# SD_Card_Interface.net
KiCad netlist of a schematic drawn in Altium Designer
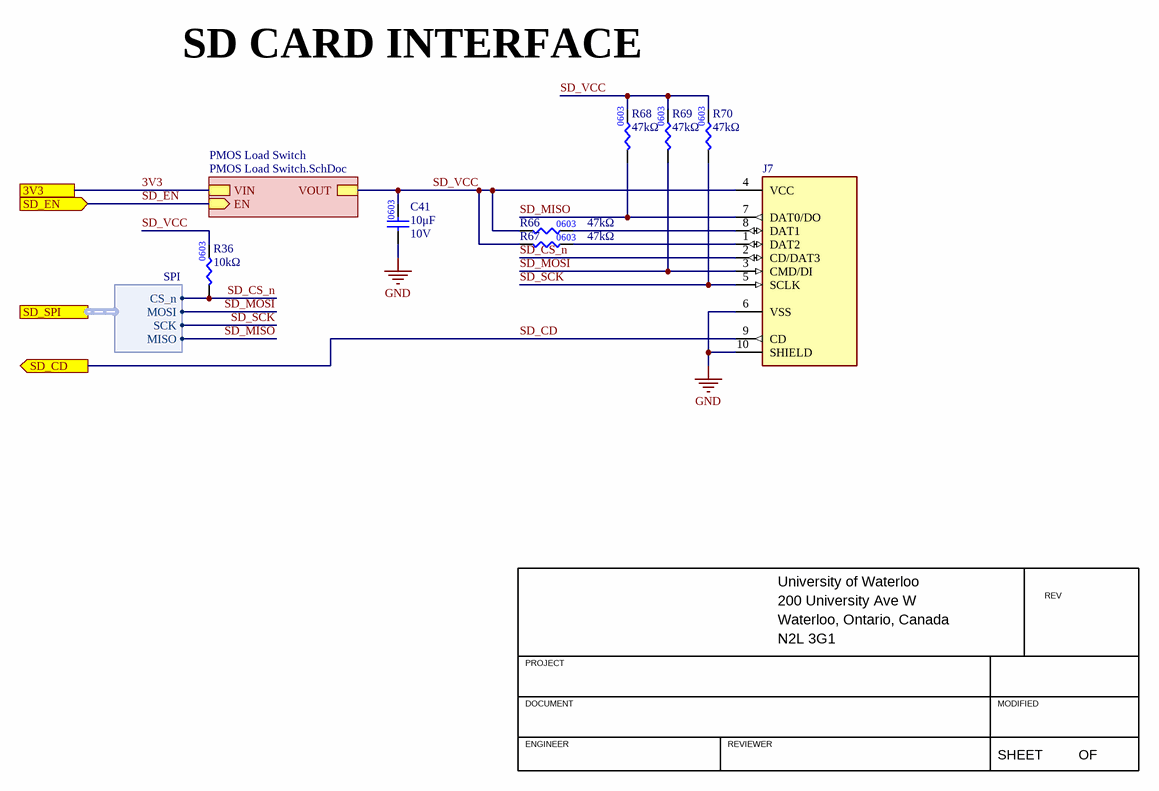
[diagram p0: SD Card Interface.SchDoc]

(export (version "E")
  (design (tool "Eeschema 10.0.6"))
  (components
    (comp (ref "C41")
      (value "10μF")
      (footprint "CAP0603")
      (description "CAP CER 10UF 10V X5R 0603")
      (fields (field (name "VOLTAGE RATING") "10V") (field (name "Comment") "CAP_10uF_10V_0603"))
      (libsource (lib "Personal_Schematic_Library_2022") (part "CAP_10uF_10V_0603"))
    )
    (comp (ref "J7")
      (value "CON_MICROSD_MOLEX")
      (footprint "MOLEX-5033981892")
      (description "CONN MICRO SD CARD R/A SMD")
      (libsource (lib "Personal_Schematic_Library_2022") (part "CON_MICROSD_MOLEX"))
    )
    (comp (ref "R36")
      (value "10kΩ")
      (footprint "RES0603")
      (description "RES 10K OHM 1% 1/8W 0603")
      (fields (field (name "Comment") "RES_10kΩ_0603_1%"))
      (libsource (lib "Personal_Schematic_Library_2022") (part "RES_10kΩ_0603_1%"))
    )
    (comp (ref "R66")
      (value "47kΩ")
      (footprint "RES0603")
      (description "RES 47K OHM 1% 1/10W 0603")
      (fields (field (name "Comment") "RES_47kΩ_0603_1%"))
      (libsource (lib "Personal_Schematic_Library_2022") (part "RES_47kΩ_0603_1%"))
    )
    (comp (ref "R67")
      (value "47kΩ")
      (footprint "RES0603")
      (description "RES 47K OHM 1% 1/10W 0603")
      (fields (field (name "Comment") "RES_47kΩ_0603_1%"))
      (libsource (lib "Personal_Schematic_Library_2022") (part "RES_47kΩ_0603_1%"))
    )
    (comp (ref "R68")
      (value "47kΩ")
      (footprint "RES0603")
      (description "RES 47K OHM 1% 1/10W 0603")
      (fields (field (name "Comment") "RES_47kΩ_0603_1%"))
      (libsource (lib "Personal_Schematic_Library_2022") (part "RES_47kΩ_0603_1%"))
    )
    (comp (ref "R69")
      (value "47kΩ")
      (footprint "RES0603")
      (description "RES 47K OHM 1% 1/10W 0603")
      (fields (field (name "Comment") "RES_47kΩ_0603_1%"))
      (libsource (lib "Personal_Schematic_Library_2022") (part "RES_47kΩ_0603_1%"))
    )
    (comp (ref "R70")
      (value "47kΩ")
      (footprint "RES0603")
      (description "RES 47K OHM 1% 1/10W 0603")
      (fields (field (name "Comment") "RES_47kΩ_0603_1%"))
      (libsource (lib "Personal_Schematic_Library_2022") (part "RES_47kΩ_0603_1%"))
    )
  )
  (nets
    (net (code "3") (name "/SD_CD") (class "Default")
      (node (ref "J7") (pin "9") (pinfunction "CD_9") (pintype "output"))
    )
    (net (code "4") (name "/SD_CS_n") (class "Default")
      (node (ref "J7") (pin "2") (pinfunction "CD/DAT3_2") (pintype "bidirectional"))
      (node (ref "R36") (pin "1") (pinfunction "1_1") (pintype "passive"))
    )
    (net (code "6") (name "/SD_MISO") (class "Default")
      (node (ref "J7") (pin "7") (pinfunction "DAT0/DO_7") (pintype "output"))
      (node (ref "R68") (pin "1") (pinfunction "1_1") (pintype "passive"))
    )
    (net (code "7") (name "/SD_MOSI") (class "Default")
      (node (ref "J7") (pin "3") (pinfunction "CMD/DI_3") (pintype "input"))
      (node (ref "R69") (pin "1") (pinfunction "1_1") (pintype "passive"))
    )
    (net (code "8") (name "/SD_SCK") (class "Default")
      (node (ref "J7") (pin "5") (pinfunction "SCLK_5") (pintype "input"))
      (node (ref "R70") (pin "1") (pinfunction "1_1") (pintype "passive"))
    )
    (net (code "9") (name "/SD_VCC") (class "Default")
      (node (ref "C41") (pin "2") (pinfunction "2_2") (pintype "passive"))
      (node (ref "J7") (pin "4") (pinfunction "VCC_4") (pintype "power_in"))
      (node (ref "R36") (pin "2") (pinfunction "2_2") (pintype "passive"))
      (node (ref "R66") (pin "1") (pinfunction "1_1") (pintype "passive"))
      (node (ref "R67") (pin "1") (pinfunction "1_1") (pintype "passive"))
      (node (ref "R68") (pin "2") (pinfunction "2_2") (pintype "passive"))
      (node (ref "R69") (pin "2") (pinfunction "2_2") (pintype "passive"))
      (node (ref "R70") (pin "2") (pinfunction "2_2") (pintype "passive"))
    )
    (net (code "11") (name "GND") (class "Default")
      (node (ref "C41") (pin "1") (pinfunction "1_1") (pintype "passive"))
      (node (ref "J7") (pin "10") (pinfunction "SHIELD_10") (pintype "passive"))
      (node (ref "J7") (pin "6") (pinfunction "VSS_6") (pintype "power_in"))
    )
    (net (code "12") (name "Net-(J7-DAT1)") (class "Default")
      (node (ref "J7") (pin "8") (pinfunction "DAT1_8") (pintype "bidirectional"))
      (node (ref "R66") (pin "2") (pinfunction "2_2") (pintype "passive"))
    )
    (net (code "13") (name "Net-(J7-DAT2)") (class "Default")
      (node (ref "J7") (pin "1") (pinfunction "DAT2_1") (pintype "bidirectional"))
      (node (ref "R67") (pin "2") (pinfunction "2_2") (pintype "passive"))
    )
  )
)
